# design.net
KiCad netlist of a schematic drawn in Altium Designer
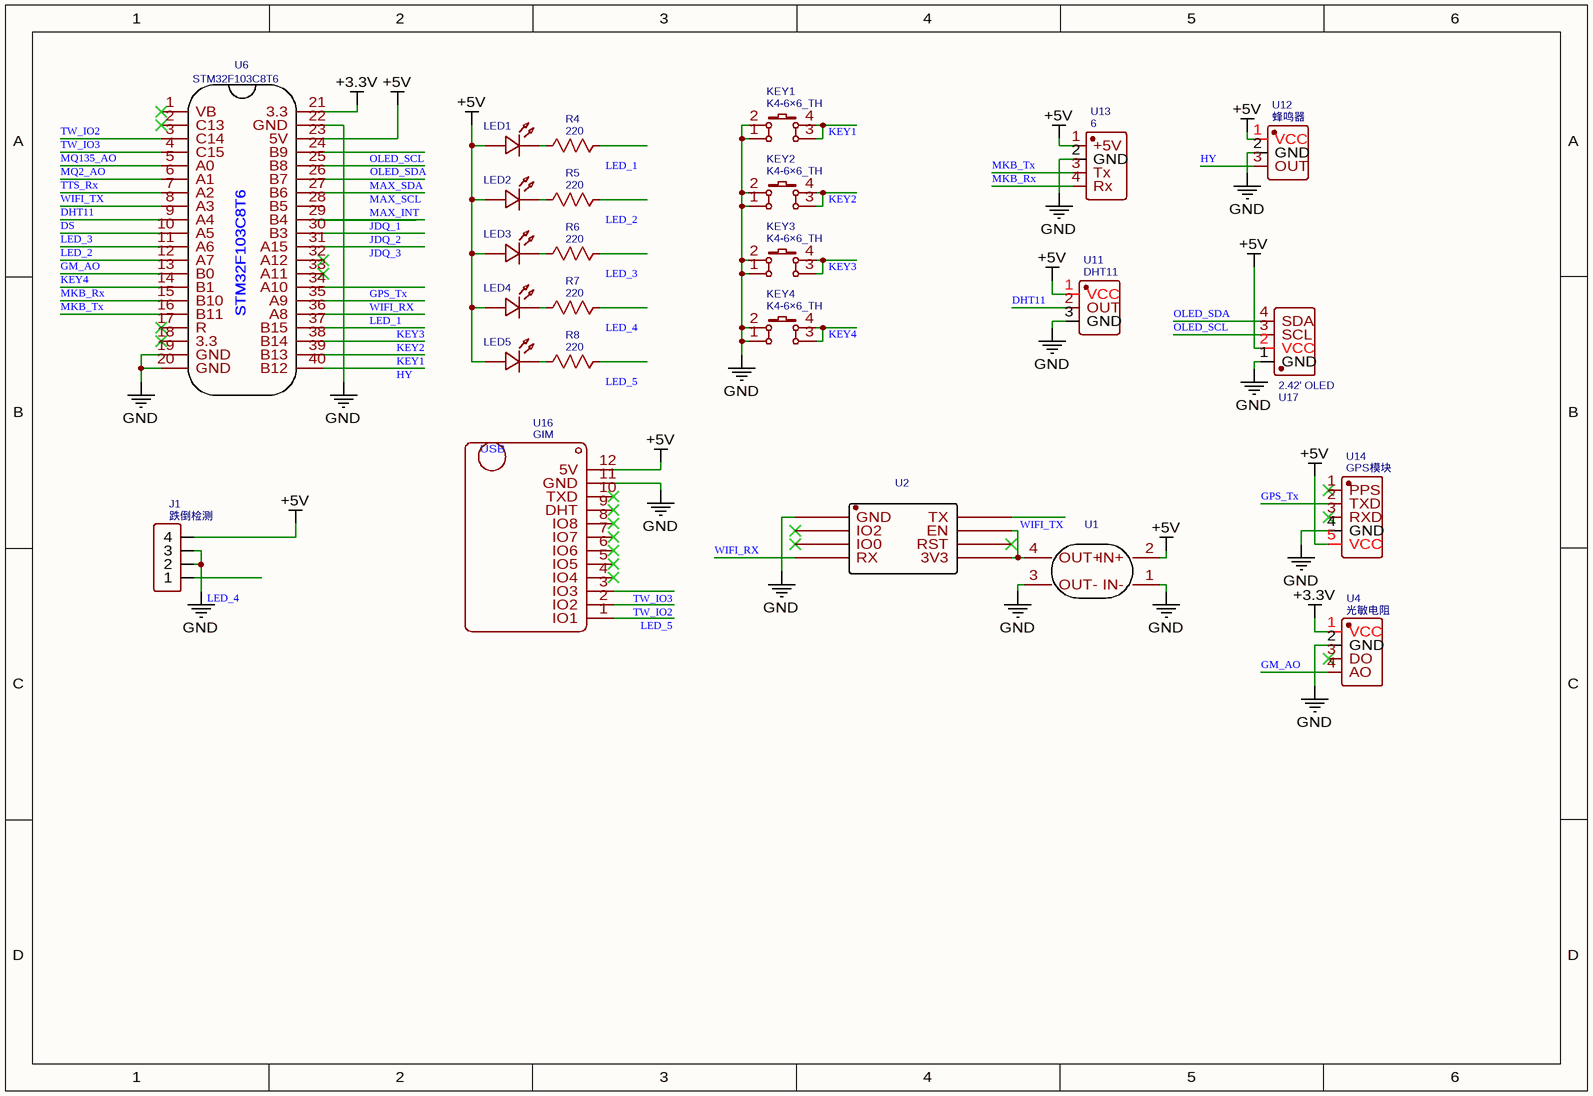
[diagram p0: 原理图.schdoc]

(export (version "E")
  (design (tool "Eeschema 10.0.6"))
  (components
    (comp (ref "J1")
      (value "跌倒检测")
      (footprint "HDR-M-2.54_1X4")
      (fields (field (name "CONTRIBUTOR") "LCEDA_Lib"))
      (libsource (lib "altium-import") (part "root_2_HDR-M-2.54_1x4_"))
    )
    (comp (ref "KEY1")
      (value "K4-6×6_TH")
      (footprint "KEY-TH_4P-L6.0-W6.0-P4.50-LS6.5")
      (fields
        (field (name "MANUFACTURER") "韩国韩荣")
        (field (name "MANUFACTURER PART") "K2-1102DP-E4SW-04")
        (field (name "CONTRIBUTOR") "LCEDA_Lib")
      )
      (libsource (lib "altium-import") (part "root_0_K4-6×6_TH_"))
    )
    (comp (ref "KEY2")
      (value "K4-6×6_TH")
      (footprint "KEY-TH_4P-L6.0-W6.0-P4.50-LS6.5")
      (fields
        (field (name "MANUFACTURER") "韩国韩荣")
        (field (name "MANUFACTURER PART") "K2-1102DP-E4SW-04")
        (field (name "CONTRIBUTOR") "LCEDA_Lib")
      )
      (libsource (lib "altium-import") (part "root_0_K4-6×6_TH_"))
    )
    (comp (ref "KEY3")
      (value "K4-6×6_TH")
      (footprint "KEY-TH_4P-L6.0-W6.0-P4.50-LS6.5")
      (fields
        (field (name "MANUFACTURER") "韩国韩荣")
        (field (name "MANUFACTURER PART") "K2-1102DP-E4SW-04")
        (field (name "CONTRIBUTOR") "LCEDA_Lib")
      )
      (libsource (lib "altium-import") (part "root_0_K4-6×6_TH_"))
    )
    (comp (ref "KEY4")
      (value "K4-6×6_TH")
      (footprint "KEY-TH_4P-L6.0-W6.0-P4.50-LS6.5")
      (fields
        (field (name "MANUFACTURER") "韩国韩荣")
        (field (name "MANUFACTURER PART") "K2-1102DP-E4SW-04")
        (field (name "CONTRIBUTOR") "LCEDA_Lib")
      )
      (libsource (lib "altium-import") (part "root_0_K4-6×6_TH_"))
    )
    (comp (ref "LED1")
      (value "LED-TH-3mm_R")
      (footprint "LED-TH_BD3.0_RED")
      (fields
        (field (name "MANUFACTURER") "EVERLIGHT(台湾亿光)")
        (field (name "MANUFACTURER PART") "204-10SDRD/S530-A3-L")
        (field (name "CONTRIBUTOR") "LCEDA_Lib")
      )
      (libsource (lib "altium-import") (part "root_0_LED-TH-3mm_R_"))
    )
    (comp (ref "LED2")
      (value "LED-TH-3mm_G")
      (footprint "LED-TH_BD3.0_GREEN")
      (fields
        (field (name "MANUFACTURER") "EVERLIGHT(台湾亿光)")
        (field (name "MANUFACTURER PART") "204-10SYGD/S530-E3")
        (field (name "CONTRIBUTOR") "LCEDA_Lib")
      )
      (libsource (lib "altium-import") (part "root_0_LED-TH-3mm_G_"))
    )
    (comp (ref "LED3")
      (value "LED-TH-3mm_G")
      (footprint "LED-TH_BD3.0_GREEN")
      (fields
        (field (name "MANUFACTURER") "EVERLIGHT(台湾亿光)")
        (field (name "MANUFACTURER PART") "204-10SYGD/S530-E3")
        (field (name "CONTRIBUTOR") "LCEDA_Lib")
      )
      (libsource (lib "altium-import") (part "root_0_LED-TH-3mm_G_"))
    )
    (comp (ref "LED4")
      (value "LED-TH-3mm_G")
      (footprint "LED-TH_BD3.0_GREEN")
      (fields
        (field (name "MANUFACTURER") "EVERLIGHT(台湾亿光)")
        (field (name "MANUFACTURER PART") "204-10SYGD/S530-E3")
        (field (name "CONTRIBUTOR") "LCEDA_Lib")
      )
      (libsource (lib "altium-import") (part "root_0_LED-TH-3mm_G_"))
    )
    (comp (ref "LED5")
      (value "LED-TH-3mm_G")
      (footprint "LED-TH_BD3.0_GREEN")
      (fields
        (field (name "MANUFACTURER") "EVERLIGHT(台湾亿光)")
        (field (name "MANUFACTURER PART") "204-10SYGD/S530-E3")
        (field (name "CONTRIBUTOR") "LCEDA_Lib")
      )
      (libsource (lib "altium-import") (part "root_0_LED-TH-3mm_G_"))
    )
    (comp (ref "R4")
      (value "220")
      (footprint "R_AXIAL-0.3")
      (fields (field (name "CONTRIBUTOR") "LCEDA_Lib"))
      (libsource (lib "altium-import") (part "root_0_220_"))
    )
    (comp (ref "R5")
      (value "220")
      (footprint "R_AXIAL-0.3")
      (fields (field (name "CONTRIBUTOR") "LCEDA_Lib"))
      (libsource (lib "altium-import") (part "root_0_220_"))
    )
    (comp (ref "R6")
      (value "220")
      (footprint "R_AXIAL-0.3")
      (fields (field (name "CONTRIBUTOR") "LCEDA_Lib"))
      (libsource (lib "altium-import") (part "root_0_220_"))
    )
    (comp (ref "R7")
      (value "220")
      (footprint "R_AXIAL-0.3")
      (fields (field (name "CONTRIBUTOR") "LCEDA_Lib"))
      (libsource (lib "altium-import") (part "root_0_220_"))
    )
    (comp (ref "R8")
      (value "220")
      (footprint "R_AXIAL-0.3")
      (fields (field (name "CONTRIBUTOR") "LCEDA_Lib"))
      (libsource (lib "altium-import") (part "root_0_220_"))
    )
    (comp (ref "U1")
      (value "NO")
      (footprint "3.3V稳压模块")
      (fields (field (name "CONTRIBUTOR") "littlebai"))
      (libsource (lib "altium-import") (part "root_2_NO_"))
    )
    (comp (ref "U2")
      (value "NO")
      (footprint "ESP8266-01S")
      (fields (field (name "CONTRIBUTOR") "Eenglish"))
      (libsource (lib "altium-import") (part "root_0_NO_"))
    )
    (comp (ref "U4")
      (value "光敏电阻")
      (footprint "HDR-M-2.54_1X4")
      (libsource (lib "altium-import") (part "root_0_光敏电阻_"))
    )
    (comp (ref "U6")
      (value "STM32F103C8T6")
      (footprint "STM32F103C8T6")
      (fields (field (name "CONTRIBUTOR") "ab_cd"))
      (libsource (lib "altium-import") (part "root_0_STM32F103C8T6_"))
    )
    (comp (ref "U11")
      (value "DHT11")
      (footprint "HDR-M-2.54_1X3")
      (libsource (lib "altium-import") (part "root_0_DHT11_"))
    )
    (comp (ref "U12")
      (value "蜂鸣器")
      (footprint "HDR-M-2.54_1X3")
      (libsource (lib "altium-import") (part "root_0_火焰传感器_"))
    )
    (comp (ref "U13")
      (value "6")
      (footprint "HDR-M-2.54_1X4")
      (libsource (lib "altium-import") (part "root_0_MKB0805_"))
    )
    (comp (ref "U14")
      (value "GPS模块")
      (footprint "HDR-M-2.54_1X5")
      (libsource (lib "altium-import") (part "root_0_GPS模块_"))
    )
    (comp (ref "U16")
      (value "GIM")
      (footprint "LU-ASR01")
      (fields (field (name "CONTRIBUTOR") "tokite"))
      (libsource (lib "altium-import") (part "root_0_天问语音模块 COPY_"))
    )
    (comp (ref "U17")
      (value "2.42' OLED")
      (footprint "HDR-M-2.54_1X4")
      (libsource (lib "altium-import") (part "root_0_2.42' OLED_"))
    )
  )
  (nets
    (net (code "1") (name "+3.3V") (class "Default")
      (node (ref "U4") (pin "1") (pinfunction "VCC_1") (pintype "passive"))
      (node (ref "U6") (pin "21") (pinfunction "3.3_21") (pintype "passive"))
    )
    (net (code "2") (name "+5V") (class "Default")
      (node (ref "J1") (pin "4") (pinfunction "4_4") (pintype "passive"))
      (node (ref "LED1") (pin "1") (pinfunction "1_1") (pintype "passive"))
      (node (ref "LED2") (pin "1") (pinfunction "1_1") (pintype "passive"))
      (node (ref "LED3") (pin "1") (pinfunction "1_1") (pintype "passive"))
      (node (ref "LED4") (pin "1") (pinfunction "1_1") (pintype "passive"))
      (node (ref "LED5") (pin "1") (pinfunction "1_1") (pintype "passive"))
      (node (ref "U1") (pin "2") (pinfunction "IN+_2") (pintype "passive"))
      (node (ref "U11") (pin "1") (pinfunction "VCC_1") (pintype "passive"))
      (node (ref "U12") (pin "1") (pinfunction "VCC_1") (pintype "passive"))
      (node (ref "U13") (pin "1") (pinfunction "+5V_1") (pintype "passive"))
      (node (ref "U14") (pin "5") (pinfunction "VCC_5") (pintype "passive"))
      (node (ref "U16") (pin "12") (pinfunction "5V_12") (pintype "passive"))
      (node (ref "U17") (pin "2") (pinfunction "VCC_2") (pintype "passive"))
      (node (ref "U6") (pin "23") (pinfunction "5V_23") (pintype "passive"))
    )
    (net (code "3") (name "/DHT11") (class "Default")
      (node (ref "U11") (pin "2") (pinfunction "OUT_2") (pintype "passive"))
      (node (ref "U6") (pin "9") (pinfunction "A4_9") (pintype "passive"))
    )
    (net (code "4") (name "/DS") (class "Default")
      (node (ref "U6") (pin "10") (pinfunction "A5_10") (pintype "passive"))
    )
    (net (code "5") (name "/GM_AO") (class "Default")
      (node (ref "U4") (pin "4") (pinfunction "AO_4") (pintype "passive"))
      (node (ref "U6") (pin "13") (pinfunction "B0_13") (pintype "passive"))
    )
    (net (code "6") (name "/GPS_Tx") (class "Default")
      (node (ref "U14") (pin "2") (pinfunction "TXD_2") (pintype "passive"))
    )
    (net (code "7") (name "/HY") (class "Default")
      (node (ref "U12") (pin "3") (pinfunction "OUT_3") (pintype "passive"))
    )
    (net (code "14") (name "/KEY4") (class "Default")
      (node (ref "U6") (pin "14") (pinfunction "B1_14") (pintype "passive"))
    )
    (net (code "16") (name "/LED_2") (class "Default")
      (node (ref "U6") (pin "12") (pinfunction "A7_12") (pintype "passive"))
    )
    (net (code "17") (name "/LED_3") (class "Default")
      (node (ref "U6") (pin "11") (pinfunction "A6_11") (pintype "passive"))
    )
    (net (code "19") (name "/LED_5") (class "Default")
      (node (ref "U16") (pin "1") (pinfunction "IO1_1") (pintype "passive"))
    )
    (net (code "23") (name "/MKB_Rx") (class "Default")
      (node (ref "U13") (pin "4") (pinfunction "Rx_4") (pintype "passive"))
      (node (ref "U6") (pin "15") (pinfunction "B10_15") (pintype "passive"))
    )
    (net (code "24") (name "/MKB_Tx") (class "Default")
      (node (ref "U13") (pin "3") (pinfunction "Tx_3") (pintype "passive"))
      (node (ref "U6") (pin "16") (pinfunction "B11_16") (pintype "passive"))
    )
    (net (code "25") (name "/MQ2_AO") (class "Default")
      (node (ref "U6") (pin "6") (pinfunction "A1_6") (pintype "passive"))
    )
    (net (code "26") (name "/MQ135_AO") (class "Default")
      (node (ref "U6") (pin "5") (pinfunction "A0_5") (pintype "passive"))
    )
    (net (code "27") (name "/OLED_SCL") (class "Default")
      (node (ref "U17") (pin "3") (pinfunction "SCL_3") (pintype "passive"))
    )
    (net (code "28") (name "/OLED_SDA") (class "Default")
      (node (ref "U17") (pin "4") (pinfunction "SDA_4") (pintype "passive"))
      (node (ref "U6") (pin "26") (pinfunction "B7_26") (pintype "passive"))
    )
    (net (code "29") (name "/TTS_Rx") (class "Default")
      (node (ref "U6") (pin "7") (pinfunction "A2_7") (pintype "passive"))
    )
    (net (code "30") (name "/TW_IO2") (class "Default")
      (node (ref "U16") (pin "2") (pinfunction "IO2_2") (pintype "passive"))
      (node (ref "U6") (pin "3") (pinfunction "C14_3") (pintype "passive"))
    )
    (net (code "31") (name "/TW_IO3") (class "Default")
      (node (ref "U16") (pin "3") (pinfunction "IO3_3") (pintype "passive"))
      (node (ref "U6") (pin "4") (pinfunction "C15_4") (pintype "passive"))
    )
    (net (code "32") (name "/WIFI_RX") (class "Default")
      (node (ref "U2") (pin "4") (pinfunction "RX_4") (pintype "passive"))
    )
    (net (code "33") (name "/WIFI_TX") (class "Default")
      (node (ref "U2") (pin "8") (pinfunction "TX_8") (pintype "passive"))
      (node (ref "U6") (pin "8") (pinfunction "A3_8") (pintype "passive"))
    )
    (net (code "34") (name "GND") (class "Default")
      (node (ref "J1") (pin "2") (pinfunction "2_2") (pintype "passive"))
      (node (ref "J1") (pin "3") (pinfunction "3_3") (pintype "passive"))
      (node (ref "KEY1") (pin "1") (pinfunction "1_1") (pintype "passive"))
      (node (ref "KEY1") (pin "2") (pinfunction "2_2") (pintype "passive"))
      (node (ref "KEY2") (pin "1") (pinfunction "1_1") (pintype "passive"))
      (node (ref "KEY2") (pin "2") (pinfunction "2_2") (pintype "passive"))
      (node (ref "KEY3") (pin "1") (pinfunction "1_1") (pintype "passive"))
      (node (ref "KEY3") (pin "2") (pinfunction "2_2") (pintype "passive"))
      (node (ref "KEY4") (pin "1") (pinfunction "1_1") (pintype "passive"))
      (node (ref "KEY4") (pin "2") (pinfunction "2_2") (pintype "passive"))
      (node (ref "U1") (pin "1") (pinfunction "IN-_1") (pintype "passive"))
      (node (ref "U1") (pin "3") (pinfunction "OUT-_3") (pintype "passive"))
      (node (ref "U11") (pin "3") (pinfunction "GND_3") (pintype "passive"))
      (node (ref "U12") (pin "2") (pinfunction "GND_2") (pintype "passive"))
      (node (ref "U13") (pin "2") (pinfunction "GND_2") (pintype "passive"))
      (node (ref "U14") (pin "4") (pinfunction "GND_4") (pintype "passive"))
      (node (ref "U16") (pin "11") (pinfunction "GND_11") (pintype "passive"))
      (node (ref "U17") (pin "1") (pinfunction "GND_1") (pintype "passive"))
      (node (ref "U2") (pin "1") (pinfunction "GND_1") (pintype "passive"))
      (node (ref "U4") (pin "2") (pinfunction "GND_2") (pintype "passive"))
      (node (ref "U6") (pin "19") (pinfunction "GND_19") (pintype "passive"))
      (node (ref "U6") (pin "20") (pinfunction "GND_20") (pintype "passive"))
      (node (ref "U6") (pin "22") (pinfunction "GND_22") (pintype "passive"))
    )
    (net (code "35") (name "Net-(KEY1-Pad3)") (class "Default")
      (node (ref "KEY1") (pin "3") (pinfunction "3_3") (pintype "passive"))
      (node (ref "KEY1") (pin "4") (pinfunction "4_4") (pintype "passive"))
    )
    (net (code "36") (name "Net-(KEY2-Pad3)") (class "Default")
      (node (ref "KEY2") (pin "3") (pinfunction "3_3") (pintype "passive"))
      (node (ref "KEY2") (pin "4") (pinfunction "4_4") (pintype "passive"))
    )
    (net (code "37") (name "Net-(KEY3-Pad3)") (class "Default")
      (node (ref "KEY3") (pin "3") (pinfunction "3_3") (pintype "passive"))
      (node (ref "KEY3") (pin "4") (pinfunction "4_4") (pintype "passive"))
    )
    (net (code "38") (name "Net-(KEY4-Pad3)") (class "Default")
      (node (ref "KEY4") (pin "3") (pinfunction "3_3") (pintype "passive"))
      (node (ref "KEY4") (pin "4") (pinfunction "4_4") (pintype "passive"))
    )
    (net (code "39") (name "Net-(LED1-Pad2)") (class "Default")
      (node (ref "LED1") (pin "2") (pinfunction "2_2") (pintype "passive"))
      (node (ref "R4") (pin "1") (pinfunction "1_1") (pintype "passive"))
    )
    (net (code "40") (name "Net-(LED2-Pad2)") (class "Default")
      (node (ref "LED2") (pin "2") (pinfunction "2_2") (pintype "passive"))
      (node (ref "R5") (pin "1") (pinfunction "1_1") (pintype "passive"))
    )
    (net (code "41") (name "Net-(LED3-Pad2)") (class "Default")
      (node (ref "LED3") (pin "2") (pinfunction "2_2") (pintype "passive"))
      (node (ref "R6") (pin "1") (pinfunction "1_1") (pintype "passive"))
    )
    (net (code "42") (name "Net-(LED4-Pad2)") (class "Default")
      (node (ref "LED4") (pin "2") (pinfunction "2_2") (pintype "passive"))
      (node (ref "R7") (pin "1") (pinfunction "1_1") (pintype "passive"))
    )
    (net (code "43") (name "Net-(LED5-Pad2)") (class "Default")
      (node (ref "LED5") (pin "2") (pinfunction "2_2") (pintype "passive"))
      (node (ref "R8") (pin "1") (pinfunction "1_1") (pintype "passive"))
    )
    (net (code "44") (name "Net-(U1-OUT+)") (class "Default")
      (node (ref "U1") (pin "4") (pinfunction "OUT+_4") (pintype "passive"))
      (node (ref "U2") (pin "5") (pinfunction "3V3_5") (pintype "passive"))
      (node (ref "U2") (pin "7") (pinfunction "EN_7") (pintype "passive"))
    )
    (net (code "45") (name "unconnected-(J1-Pad1)") (class "Default")
      (node (ref "J1") (pin "1") (pinfunction "1_1") (pintype "passive"))
    )
    (net (code "46") (name "unconnected-(R4-Pad2)") (class "Default")
      (node (ref "R4") (pin "2") (pinfunction "2_2") (pintype "passive"))
    )
    (net (code "47") (name "unconnected-(R5-Pad2)") (class "Default")
      (node (ref "R5") (pin "2") (pinfunction "2_2") (pintype "passive"))
    )
    (net (code "48") (name "unconnected-(R6-Pad2)") (class "Default")
      (node (ref "R6") (pin "2") (pinfunction "2_2") (pintype "passive"))
    )
    (net (code "49") (name "unconnected-(R7-Pad2)") (class "Default")
      (node (ref "R7") (pin "2") (pinfunction "2_2") (pintype "passive"))
    )
    (net (code "50") (name "unconnected-(R8-Pad2)") (class "Default")
      (node (ref "R8") (pin "2") (pinfunction "2_2") (pintype "passive"))
    )
    (net (code "51") (name "unconnected-(U2-IO0-Pad3)") (class "Default")
      (node (ref "U2") (pin "3") (pinfunction "IO0_3") (pintype "passive+no_connect"))
    )
    (net (code "52") (name "unconnected-(U2-IO2-Pad2)") (class "Default")
      (node (ref "U2") (pin "2") (pinfunction "IO2_2") (pintype "passive+no_connect"))
    )
    (net (code "53") (name "unconnected-(U2-RST-Pad6)") (class "Default")
      (node (ref "U2") (pin "6") (pinfunction "RST_6") (pintype "passive+no_connect"))
    )
    (net (code "54") (name "unconnected-(U4-DO-Pad3)") (class "Default")
      (node (ref "U4") (pin "3") (pinfunction "DO_3") (pintype "passive+no_connect"))
    )
    (net (code "55") (name "unconnected-(U6-3.3-Pad18)") (class "Default")
      (node (ref "U6") (pin "18") (pinfunction "3.3_18") (pintype "passive+no_connect"))
    )
    (net (code "56") (name "unconnected-(U6-A8-Pad36)") (class "Default")
      (node (ref "U6") (pin "36") (pinfunction "A8_36") (pintype "passive"))
    )
    (net (code "57") (name "unconnected-(U6-A9-Pad35)") (class "Default")
      (node (ref "U6") (pin "35") (pinfunction "A9_35") (pintype "passive"))
    )
    (net (code "58") (name "unconnected-(U6-A10-Pad34)") (class "Default")
      (node (ref "U6") (pin "34") (pinfunction "A10_34") (pintype "passive"))
    )
    (net (code "59") (name "unconnected-(U6-A11-Pad33)") (class "Default")
      (node (ref "U6") (pin "33") (pinfunction "A11_33") (pintype "passive+no_connect"))
    )
    (net (code "60") (name "unconnected-(U6-A12-Pad32)") (class "Default")
      (node (ref "U6") (pin "32") (pinfunction "A12_32") (pintype "passive+no_connect"))
    )
    (net (code "61") (name "unconnected-(U6-A15-Pad31)") (class "Default")
      (node (ref "U6") (pin "31") (pinfunction "A15_31") (pintype "passive"))
    )
    (net (code "62") (name "unconnected-(U6-B3-Pad30)") (class "Default")
      (node (ref "U6") (pin "30") (pinfunction "B3_30") (pintype "passive"))
    )
    (net (code "63") (name "unconnected-(U6-B4-Pad29)") (class "Default")
      (node (ref "U6") (pin "29") (pinfunction "B4_29") (pintype "passive"))
    )
    (net (code "64") (name "unconnected-(U6-B5-Pad28)") (class "Default")
      (node (ref "U6") (pin "28") (pinfunction "B5_28") (pintype "passive"))
    )
    (net (code "65") (name "unconnected-(U6-B6-Pad27)") (class "Default")
      (node (ref "U6") (pin "27") (pinfunction "B6_27") (pintype "passive"))
    )
    (net (code "66") (name "unconnected-(U6-B8-Pad25)") (class "Default")
      (node (ref "U6") (pin "25") (pinfunction "B8_25") (pintype "passive"))
    )
    (net (code "67") (name "unconnected-(U6-B9-Pad24)") (class "Default")
      (node (ref "U6") (pin "24") (pinfunction "B9_24") (pintype "passive"))
    )
    (net (code "68") (name "unconnected-(U6-B12-Pad40)") (class "Default")
      (node (ref "U6") (pin "40") (pinfunction "B12_40") (pintype "passive"))
    )
    (net (code "69") (name "unconnected-(U6-B13-Pad39)") (class "Default")
      (node (ref "U6") (pin "39") (pinfunction "B13_39") (pintype "passive"))
    )
    (net (code "70") (name "unconnected-(U6-B14-Pad38)") (class "Default")
      (node (ref "U6") (pin "38") (pinfunction "B14_38") (pintype "passive"))
    )
    (net (code "71") (name "unconnected-(U6-B15-Pad37)") (class "Default")
      (node (ref "U6") (pin "37") (pinfunction "B15_37") (pintype "passive"))
    )
    (net (code "72") (name "unconnected-(U6-C13-Pad2)") (class "Default")
      (node (ref "U6") (pin "2") (pinfunction "C13_2") (pintype "passive+no_connect"))
    )
    (net (code "73") (name "unconnected-(U6-R-Pad17)") (class "Default")
      (node (ref "U6") (pin "17") (pinfunction "R_17") (pintype "passive+no_connect"))
    )
    (net (code "74") (name "unconnected-(U6-VB-Pad1)") (class "Default")
      (node (ref "U6") (pin "1") (pinfunction "VB_1") (pintype "passive+no_connect"))
    )
    (net (code "75") (name "unconnected-(U14-PPS-Pad1)") (class "Default")
      (node (ref "U14") (pin "1") (pinfunction "PPS_1") (pintype "passive+no_connect"))
    )
    (net (code "76") (name "unconnected-(U14-RXD-Pad3)") (class "Default")
      (node (ref "U14") (pin "3") (pinfunction "RXD_3") (pintype "passive+no_connect"))
    )
    (net (code "77") (name "unconnected-(U16-DHT-Pad9)") (class "Default")
      (node (ref "U16") (pin "9") (pinfunction "DHT_9") (pintype "passive+no_connect"))
    )
    (net (code "78") (name "unconnected-(U16-IO4-Pad4)") (class "Default")
      (node (ref "U16") (pin "4") (pinfunction "IO4_4") (pintype "passive+no_connect"))
    )
    (net (code "79") (name "unconnected-(U16-IO5-Pad5)") (class "Default")
      (node (ref "U16") (pin "5") (pinfunction "IO5_5") (pintype "passive+no_connect"))
    )
    (net (code "80") (name "unconnected-(U16-IO6-Pad6)") (class "Default")
      (node (ref "U16") (pin "6") (pinfunction "IO6_6") (pintype "passive+no_connect"))
    )
    (net (code "81") (name "unconnected-(U16-IO7-Pad7)") (class "Default")
      (node (ref "U16") (pin "7") (pinfunction "IO7_7") (pintype "passive+no_connect"))
    )
    (net (code "82") (name "unconnected-(U16-IO8-Pad8)") (class "Default")
      (node (ref "U16") (pin "8") (pinfunction "IO8_8") (pintype "passive+no_connect"))
    )
    (net (code "83") (name "unconnected-(U16-TXD-Pad10)") (class "Default")
      (node (ref "U16") (pin "10") (pinfunction "TXD_10") (pintype "passive+no_connect"))
    )
  )
)
